# parallelEMtest.net
KiCad netlist of a schematic drawn in EAGLE
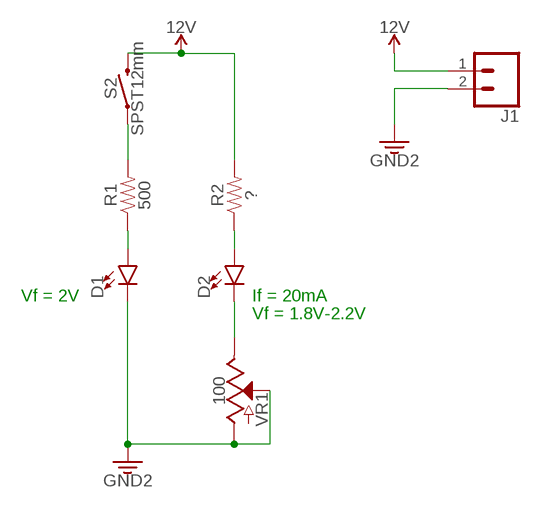
[diagram p0: schematic, sheet 1]

(export (version "E")
  (design (tool "Eeschema 10.0.6"))
  (components
    (comp (ref "D1")
      (value "LED5MM")
      (footprint "eagle-import:LED_5MM")
      (libsource (lib "eagle-import") (part "LED5MM"))
    )
    (comp (ref "D2")
      (value "LED5MM")
      (footprint "eagle-import:LED_5MM")
      (libsource (lib "eagle-import") (part "LED5MM"))
    )
    (comp (ref "J1")
      (value "CONN_02PTH4")
      (footprint "eagle-import:1X02_XTRA_BIG")
      (libsource (lib "eagle-import") (part "CONN_02PTH4"))
    )
    (comp (ref "R1")
      (value "500")
      (footprint "eagle-import:AXIAL-0.3")
      (libsource (lib "eagle-import") (part "RESISTORAXIAL-0.3"))
    )
    (comp (ref "R2")
      (value "?")
      (footprint "eagle-import:AXIAL-0.3")
      (libsource (lib "eagle-import") (part "RESISTORAXIAL-0.3"))
    )
    (comp (ref "S2")
      (value "SPST12mm")
      (footprint "eagle-import:TACTILE_SWITCH_PTH_12MM")
      (libsource (lib "eagle-import") (part "MOMENTARY-SWITCH-SPST-PTH-12MM"))
    )
    (comp (ref "VR1")
      (value "100")
      (footprint "eagle-import:POT-PTH-ALPS")
      (libsource (lib "eagle-import") (part "POTENTIOMETER-PTH-9MM-1/20W-20%"))
    )
  )
  (nets
    (net (code "1") (name "12V") (class "Default")
      (node (ref "J1") (pin "1") (pinfunction "1_1") (pintype "passive"))
      (node (ref "R2") (pin "P$2") (pinfunction "2_P$2") (pintype "passive"))
      (node (ref "S2") (pin "3") (pinfunction "2_3") (pintype "passive"))
    )
    (net (code "2") (name "GND2") (class "Default")
      (node (ref "D1") (pin "K") (pinfunction "C_K") (pintype "passive"))
      (node (ref "J1") (pin "2") (pinfunction "2_2") (pintype "passive"))
      (node (ref "VR1") (pin "P$2") (pinfunction "S_P$2") (pintype "passive"))
      (node (ref "VR1") (pin "P$3") (pinfunction "A_P$3") (pintype "passive"))
    )
    (net (code "3") (name "Net-(D2-C)") (class "Default")
      (node (ref "D2") (pin "K") (pinfunction "C_K") (pintype "passive"))
      (node (ref "VR1") (pin "P$1") (pinfunction "E_P$1") (pintype "passive"))
    )
    (net (code "4") (name "Net-(R1-1)") (class "Default")
      (node (ref "D1") (pin "A") (pinfunction "A_A") (pintype "passive"))
      (node (ref "R1") (pin "P$1") (pinfunction "1_P$1") (pintype "passive"))
    )
    (net (code "5") (name "Net-(R1-2)") (class "Default")
      (node (ref "R1") (pin "P$2") (pinfunction "2_P$2") (pintype "passive"))
      (node (ref "S2") (pin "1") (pinfunction "1_1") (pintype "passive"))
    )
    (net (code "6") (name "Net-(R2-1)") (class "Default")
      (node (ref "D2") (pin "A") (pinfunction "A_A") (pintype "passive"))
      (node (ref "R2") (pin "P$1") (pinfunction "1_P$1") (pintype "passive"))
    )
  )
)
